# auxboxshield1_42.net
KiCad netlist of a schematic drawn in EAGLE
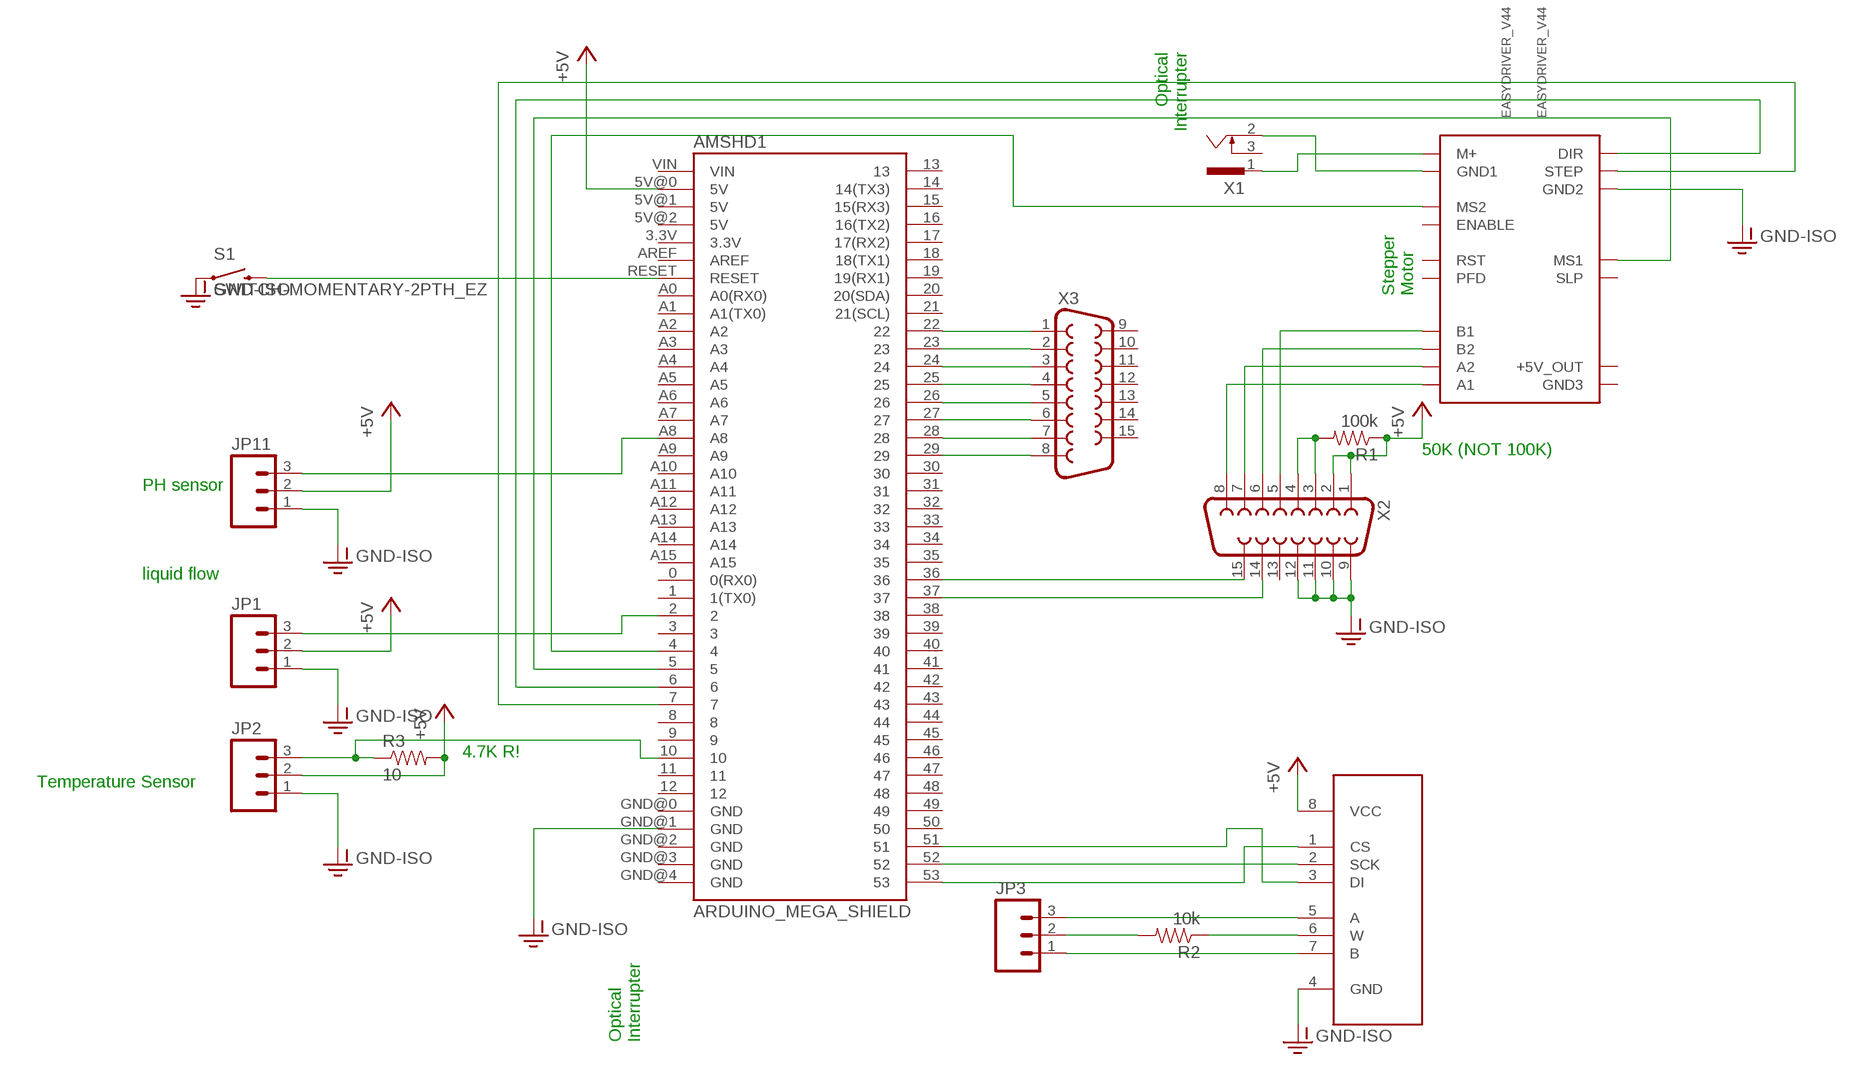
[diagram p0: schematic, sheet 1]

(export (version "E")
  (design (tool "Eeschema 10.0.6"))
  (components
    (comp (ref "AMSHD1")
      (value "ARDUINO_MEGA_SHIELD")
      (footprint "eagle-import:ARDUINO_MEGA_SHIELD")
      (libsource (lib "eagle-import") (part "ARDUINO_MEGA_SHIELD"))
    )
    (comp (ref "EASYDRIVER_V44")
      (value "EASYDRIVER_V44")
      (footprint "eagle-import:EASYDRIVER_V44")
      (libsource (lib "eagle-import") (part "EASYDRIVER_V44"))
    )
    (comp (ref "JP1")
      (value "M03POLAR")
      (footprint "eagle-import:MOLEX-1X3")
      (libsource (lib "eagle-import") (part "M03POLAR"))
    )
    (comp (ref "JP2")
      (value "M03POLAR")
      (footprint "eagle-import:MOLEX-1X3")
      (libsource (lib "eagle-import") (part "M03POLAR"))
    )
    (comp (ref "JP3")
      (value "M03POLAR")
      (footprint "eagle-import:MOLEX-1X3")
      (libsource (lib "eagle-import") (part "M03POLAR"))
    )
    (comp (ref "JP11")
      (value "M03POLAR")
      (footprint "eagle-import:MOLEX-1X3")
      (libsource (lib "eagle-import") (part "M03POLAR"))
    )
    (comp (ref "R1")
      (value "100k")
      (footprint "eagle-import:AXIAL-0.3")
      (libsource (lib "eagle-import") (part "100KOHM-1/4W-5%(PTH)"))
    )
    (comp (ref "R2")
      (value "10k")
      (footprint "eagle-import:AXIAL-0.3")
      (libsource (lib "eagle-import") (part "10KOHM-1/4W-1%(PTH)HORIZ"))
    )
    (comp (ref "R3")
      (value "10")
      (footprint "eagle-import:AXIAL-0.3")
      (libsource (lib "eagle-import") (part "10OHM-1/4W-5%(PTH)"))
    )
    (comp (ref "S1")
      (value "SWITCH-MOMENTARY-2PTH_EZ")
      (footprint "eagle-import:TACTILE-PTH-EZ")
      (libsource (lib "eagle-import") (part "SWITCH-MOMENTARY-2PTH_EZ"))
    )
    (comp (ref "U1")
      (value "MCP41XXX")
      (footprint "eagle-import:SO08")
      (libsource (lib "eagle-import") (part "MCP41XXX"))
    )
    (comp (ref "X1")
      (value "SCD-014A")
      (footprint "eagle-import:SCD-014-A")
      (libsource (lib "eagle-import") (part "SCD-014A"))
    )
    (comp (ref "X2")
      (value "F15HP")
      (footprint "eagle-import:F15HP")
      (libsource (lib "eagle-import") (part "F15HP"))
    )
    (comp (ref "X3")
      (value "F15HP")
      (footprint "eagle-import:F15HP")
      (libsource (lib "eagle-import") (part "F15HP"))
    )
  )
  (nets
    (net (code "1") (name "+5V") (class "Default")
      (node (ref "AMSHD1") (pin "5V@0") (pinfunction "5V_5V@0") (pintype "bidirectional"))
      (node (ref "JP1") (pin "2") (pinfunction "2_2") (pintype "passive"))
      (node (ref "JP11") (pin "2") (pinfunction "2_2") (pintype "passive"))
      (node (ref "JP2") (pin "2") (pinfunction "2_2") (pintype "passive"))
      (node (ref "R1") (pin "P$1") (pinfunction "1_P$1") (pintype "passive"))
      (node (ref "R3") (pin "P$2") (pinfunction "2_P$2") (pintype "passive"))
      (node (ref "U1") (pin "8") (pinfunction "VCC_8") (pintype "bidirectional"))
      (node (ref "X2") (pin "1") (pinfunction "1_1") (pintype "passive"))
      (node (ref "X2") (pin "2") (pinfunction "2_2") (pintype "passive"))
    )
    (net (code "2") (name "GND-ISO") (class "Default")
      (node (ref "AMSHD1") (pin "GND@1") (pinfunction "GND_GND@1") (pintype "bidirectional"))
      (node (ref "EASYDRIVER_V44") (pin "GND2") (pinfunction "GND2_GND2") (pintype "bidirectional"))
      (node (ref "JP1") (pin "1") (pinfunction "1_1") (pintype "passive"))
      (node (ref "JP11") (pin "1") (pinfunction "1_1") (pintype "passive"))
      (node (ref "JP2") (pin "1") (pinfunction "1_1") (pintype "passive"))
      (node (ref "S1") (pin "1") (pinfunction "1_1") (pintype "passive"))
      (node (ref "U1") (pin "4") (pinfunction "GND_4") (pintype "bidirectional"))
      (node (ref "X2") (pin "10") (pinfunction "10_10") (pintype "passive"))
      (node (ref "X2") (pin "11") (pinfunction "11_11") (pintype "passive"))
      (node (ref "X2") (pin "12") (pinfunction "12_12") (pintype "passive"))
      (node (ref "X2") (pin "9") (pinfunction "9_9") (pintype "passive"))
    )
    (net (code "3") (name "Net-(AMSHD1-Pad2)") (class "Default")
      (node (ref "AMSHD1") (pin "2") (pinfunction "2_2") (pintype "bidirectional"))
      (node (ref "JP1") (pin "3") (pinfunction "3_3") (pintype "passive"))
    )
    (net (code "4") (name "Net-(AMSHD1-Pad4)") (class "Default")
      (node (ref "AMSHD1") (pin "4") (pinfunction "4_4") (pintype "bidirectional"))
      (node (ref "EASYDRIVER_V44") (pin "MS2") (pinfunction "MS2_MS2") (pintype "bidirectional"))
    )
    (net (code "5") (name "Net-(AMSHD1-Pad5)") (class "Default")
      (node (ref "AMSHD1") (pin "5") (pinfunction "5_5") (pintype "bidirectional"))
      (node (ref "EASYDRIVER_V44") (pin "MS1") (pinfunction "MS1_MS1") (pintype "bidirectional"))
    )
    (net (code "6") (name "Net-(AMSHD1-Pad6)") (class "Default")
      (node (ref "AMSHD1") (pin "6") (pinfunction "6_6") (pintype "bidirectional"))
      (node (ref "EASYDRIVER_V44") (pin "DIR") (pinfunction "DIR_DIR") (pintype "bidirectional"))
    )
    (net (code "7") (name "Net-(AMSHD1-Pad7)") (class "Default")
      (node (ref "AMSHD1") (pin "7") (pinfunction "7_7") (pintype "bidirectional"))
      (node (ref "EASYDRIVER_V44") (pin "STEP") (pinfunction "STEP_STEP") (pintype "bidirectional"))
    )
    (net (code "8") (name "Net-(AMSHD1-Pad22)") (class "Default")
      (node (ref "AMSHD1") (pin "22") (pinfunction "22_22") (pintype "bidirectional"))
      (node (ref "X3") (pin "1") (pinfunction "1_1") (pintype "passive"))
    )
    (net (code "9") (name "Net-(AMSHD1-Pad23)") (class "Default")
      (node (ref "AMSHD1") (pin "23") (pinfunction "23_23") (pintype "bidirectional"))
      (node (ref "X3") (pin "2") (pinfunction "2_2") (pintype "passive"))
    )
    (net (code "10") (name "Net-(AMSHD1-Pad24)") (class "Default")
      (node (ref "AMSHD1") (pin "24") (pinfunction "24_24") (pintype "bidirectional"))
      (node (ref "X3") (pin "3") (pinfunction "3_3") (pintype "passive"))
    )
    (net (code "11") (name "Net-(AMSHD1-Pad25)") (class "Default")
      (node (ref "AMSHD1") (pin "25") (pinfunction "25_25") (pintype "bidirectional"))
      (node (ref "X3") (pin "4") (pinfunction "4_4") (pintype "passive"))
    )
    (net (code "12") (name "Net-(AMSHD1-Pad26)") (class "Default")
      (node (ref "AMSHD1") (pin "26") (pinfunction "26_26") (pintype "bidirectional"))
      (node (ref "X3") (pin "5") (pinfunction "5_5") (pintype "passive"))
    )
    (net (code "13") (name "Net-(AMSHD1-Pad27)") (class "Default")
      (node (ref "AMSHD1") (pin "27") (pinfunction "27_27") (pintype "bidirectional"))
      (node (ref "X3") (pin "6") (pinfunction "6_6") (pintype "passive"))
    )
    (net (code "14") (name "Net-(AMSHD1-Pad28)") (class "Default")
      (node (ref "AMSHD1") (pin "28") (pinfunction "28_28") (pintype "bidirectional"))
      (node (ref "X3") (pin "7") (pinfunction "7_7") (pintype "passive"))
    )
    (net (code "15") (name "Net-(AMSHD1-Pad29)") (class "Default")
      (node (ref "AMSHD1") (pin "29") (pinfunction "29_29") (pintype "bidirectional"))
      (node (ref "X3") (pin "8") (pinfunction "8_8") (pintype "passive"))
    )
    (net (code "16") (name "Net-(AMSHD1-Pad36)") (class "Default")
      (node (ref "AMSHD1") (pin "36") (pinfunction "36_36") (pintype "bidirectional"))
      (node (ref "X2") (pin "15") (pinfunction "15_15") (pintype "passive"))
    )
    (net (code "17") (name "Net-(AMSHD1-Pad37)") (class "Default")
      (node (ref "AMSHD1") (pin "37") (pinfunction "37_37") (pintype "bidirectional"))
      (node (ref "X2") (pin "14") (pinfunction "14_14") (pintype "passive"))
    )
    (net (code "18") (name "Net-(AMSHD1-PadA8)") (class "Default")
      (node (ref "AMSHD1") (pin "A8") (pinfunction "A8_A8") (pintype "bidirectional"))
      (node (ref "JP11") (pin "3") (pinfunction "3_3") (pintype "passive"))
    )
    (net (code "19") (name "Net-(EASYDRIVER_V44-PadA1)") (class "Default")
      (node (ref "EASYDRIVER_V44") (pin "A1") (pinfunction "A1_A1") (pintype "bidirectional"))
      (node (ref "X2") (pin "8") (pinfunction "8_8") (pintype "passive"))
    )
    (net (code "20") (name "Net-(EASYDRIVER_V44-PadA2)") (class "Default")
      (node (ref "EASYDRIVER_V44") (pin "A2") (pinfunction "A2_A2") (pintype "bidirectional"))
      (node (ref "X2") (pin "7") (pinfunction "7_7") (pintype "passive"))
    )
    (net (code "21") (name "Net-(EASYDRIVER_V44-PadB1)") (class "Default")
      (node (ref "EASYDRIVER_V44") (pin "B1") (pinfunction "B1_B1") (pintype "bidirectional"))
      (node (ref "X2") (pin "5") (pinfunction "5_5") (pintype "passive"))
    )
    (net (code "22") (name "Net-(EASYDRIVER_V44-PadB2)") (class "Default")
      (node (ref "EASYDRIVER_V44") (pin "B2") (pinfunction "B2_B2") (pintype "bidirectional"))
      (node (ref "X2") (pin "6") (pinfunction "6_6") (pintype "passive"))
    )
    (net (code "23") (name "Net-(EASYDRIVER_V44-PadGND1)") (class "Default")
      (node (ref "EASYDRIVER_V44") (pin "GND1") (pinfunction "GND1_GND1") (pintype "bidirectional"))
      (node (ref "X1") (pin "2") (pinfunction "2_2") (pintype "passive"))
    )
    (net (code "24") (name "Net-(EASYDRIVER_V44-PadM+)") (class "Default")
      (node (ref "EASYDRIVER_V44") (pin "M+") (pinfunction "M+_M+") (pintype "bidirectional"))
      (node (ref "X1") (pin "1") (pinfunction "1_1") (pintype "passive"))
    )
    (net (code "25") (name "Net-(R1-2)") (class "Default")
      (node (ref "R1") (pin "P$2") (pinfunction "2_P$2") (pintype "passive"))
      (node (ref "X2") (pin "3") (pinfunction "3_3") (pintype "passive"))
      (node (ref "X2") (pin "4") (pinfunction "4_4") (pintype "passive"))
    )
    (net (code "26") (name "Net-(R2-1)") (class "Default")
      (node (ref "R2") (pin "P$1") (pinfunction "1_P$1") (pintype "passive"))
      (node (ref "U1") (pin "6") (pinfunction "W_6") (pintype "bidirectional"))
    )
    (net (code "27") (name "Net-(R2-2)") (class "Default")
      (node (ref "JP3") (pin "2") (pinfunction "2_2") (pintype "passive"))
      (node (ref "R2") (pin "P$2") (pinfunction "2_P$2") (pintype "passive"))
    )
    (net (code "28") (name "Net-(R3-1)") (class "Default")
      (node (ref "AMSHD1") (pin "10") (pinfunction "10_10") (pintype "bidirectional"))
      (node (ref "JP2") (pin "3") (pinfunction "3_3") (pintype "passive"))
      (node (ref "R3") (pin "P$1") (pinfunction "1_P$1") (pintype "passive"))
    )
    (net (code "29") (name "Net-(S1-2)") (class "Default")
      (node (ref "AMSHD1") (pin "RESET") (pinfunction "RESET_RESET") (pintype "bidirectional"))
      (node (ref "S1") (pin "3") (pinfunction "2_3") (pintype "passive"))
    )
    (net (code "30") (name "Net-(U1-A)") (class "Default")
      (node (ref "JP3") (pin "3") (pinfunction "3_3") (pintype "passive"))
      (node (ref "U1") (pin "5") (pinfunction "A_5") (pintype "bidirectional"))
    )
    (net (code "31") (name "Net-(U1-B)") (class "Default")
      (node (ref "JP3") (pin "1") (pinfunction "1_1") (pintype "passive"))
      (node (ref "U1") (pin "7") (pinfunction "B_7") (pintype "bidirectional"))
    )
    (net (code "32") (name "Net-(U1-CS)") (class "Default")
      (node (ref "AMSHD1") (pin "53") (pinfunction "53_53") (pintype "bidirectional"))
      (node (ref "U1") (pin "1") (pinfunction "CS_1") (pintype "bidirectional"))
    )
    (net (code "33") (name "Net-(U1-DI)") (class "Default")
      (node (ref "AMSHD1") (pin "51") (pinfunction "51_51") (pintype "bidirectional"))
      (node (ref "U1") (pin "3") (pinfunction "DI_3") (pintype "bidirectional"))
    )
    (net (code "34") (name "Net-(U1-SCK)") (class "Default")
      (node (ref "AMSHD1") (pin "52") (pinfunction "52_52") (pintype "bidirectional"))
      (node (ref "U1") (pin "2") (pinfunction "SCK_2") (pintype "bidirectional"))
    )
    (net (code "35") (name "unconnected-(AMSHD1-0(RX0)-Pad0)") (class "Default")
      (node (ref "AMSHD1") (pin "0") (pinfunction "0(RX0)_0") (pintype "bidirectional"))
    )
    (net (code "36") (name "unconnected-(AMSHD1-1(TX0)-Pad1)") (class "Default")
      (node (ref "AMSHD1") (pin "1") (pinfunction "1(TX0)_1") (pintype "bidirectional"))
    )
    (net (code "37") (name "unconnected-(AMSHD1-5V-Pad5V@1)") (class "Default")
      (node (ref "AMSHD1") (pin "5V@1") (pinfunction "5V_5V@1") (pintype "bidirectional"))
    )
    (net (code "38") (name "unconnected-(AMSHD1-5V-Pad5V@2)") (class "Default")
      (node (ref "AMSHD1") (pin "5V@2") (pinfunction "5V_5V@2") (pintype "bidirectional"))
    )
    (net (code "39") (name "unconnected-(AMSHD1-14(TX3)-Pad14)") (class "Default")
      (node (ref "AMSHD1") (pin "14") (pinfunction "14(TX3)_14") (pintype "bidirectional"))
    )
    (net (code "40") (name "unconnected-(AMSHD1-15(RX3)-Pad15)") (class "Default")
      (node (ref "AMSHD1") (pin "15") (pinfunction "15(RX3)_15") (pintype "bidirectional"))
    )
    (net (code "41") (name "unconnected-(AMSHD1-16(TX2)-Pad16)") (class "Default")
      (node (ref "AMSHD1") (pin "16") (pinfunction "16(TX2)_16") (pintype "bidirectional"))
    )
    (net (code "42") (name "unconnected-(AMSHD1-17(RX2)-Pad17)") (class "Default")
      (node (ref "AMSHD1") (pin "17") (pinfunction "17(RX2)_17") (pintype "bidirectional"))
    )
    (net (code "43") (name "unconnected-(AMSHD1-18(TX1)-Pad18)") (class "Default")
      (node (ref "AMSHD1") (pin "18") (pinfunction "18(TX1)_18") (pintype "bidirectional"))
    )
    (net (code "44") (name "unconnected-(AMSHD1-19(RX1)-Pad19)") (class "Default")
      (node (ref "AMSHD1") (pin "19") (pinfunction "19(RX1)_19") (pintype "bidirectional"))
    )
    (net (code "45") (name "unconnected-(AMSHD1-20(SDA)-Pad20)") (class "Default")
      (node (ref "AMSHD1") (pin "20") (pinfunction "20(SDA)_20") (pintype "bidirectional"))
    )
    (net (code "46") (name "unconnected-(AMSHD1-21(SCL)-Pad21)") (class "Default")
      (node (ref "AMSHD1") (pin "21") (pinfunction "21(SCL)_21") (pintype "bidirectional"))
    )
    (net (code "47") (name "unconnected-(AMSHD1-A0(RX0)-PadA0)") (class "Default")
      (node (ref "AMSHD1") (pin "A0") (pinfunction "A0(RX0)_A0") (pintype "bidirectional"))
    )
    (net (code "48") (name "unconnected-(AMSHD1-A1(TX0)-PadA1)") (class "Default")
      (node (ref "AMSHD1") (pin "A1") (pinfunction "A1(TX0)_A1") (pintype "bidirectional"))
    )
    (net (code "49") (name "unconnected-(AMSHD1-GND-PadGND@0)") (class "Default")
      (node (ref "AMSHD1") (pin "GND@0") (pinfunction "GND_GND@0") (pintype "bidirectional"))
    )
    (net (code "50") (name "unconnected-(AMSHD1-GND-PadGND@2)") (class "Default")
      (node (ref "AMSHD1") (pin "GND@2") (pinfunction "GND_GND@2") (pintype "bidirectional"))
    )
    (net (code "51") (name "unconnected-(AMSHD1-GND-PadGND@3)") (class "Default")
      (node (ref "AMSHD1") (pin "GND@3") (pinfunction "GND_GND@3") (pintype "bidirectional"))
    )
    (net (code "52") (name "unconnected-(AMSHD1-GND-PadGND@4)") (class "Default")
      (node (ref "AMSHD1") (pin "GND@4") (pinfunction "GND_GND@4") (pintype "bidirectional"))
    )
    (net (code "53") (name "unconnected-(AMSHD1-Pad3)") (class "Default")
      (node (ref "AMSHD1") (pin "3") (pinfunction "3_3") (pintype "bidirectional"))
    )
    (net (code "54") (name "unconnected-(AMSHD1-Pad3.3V)") (class "Default")
      (node (ref "AMSHD1") (pin "3.3V") (pinfunction "3.3V_3.3V") (pintype "bidirectional"))
    )
    (net (code "55") (name "unconnected-(AMSHD1-Pad8)") (class "Default")
      (node (ref "AMSHD1") (pin "8") (pinfunction "8_8") (pintype "bidirectional"))
    )
    (net (code "56") (name "unconnected-(AMSHD1-Pad9)") (class "Default")
      (node (ref "AMSHD1") (pin "9") (pinfunction "9_9") (pintype "bidirectional"))
    )
    (net (code "57") (name "unconnected-(AMSHD1-Pad11)") (class "Default")
      (node (ref "AMSHD1") (pin "11") (pinfunction "11_11") (pintype "bidirectional"))
    )
    (net (code "58") (name "unconnected-(AMSHD1-Pad12)") (class "Default")
      (node (ref "AMSHD1") (pin "12") (pinfunction "12_12") (pintype "bidirectional"))
    )
    (net (code "59") (name "unconnected-(AMSHD1-Pad13)") (class "Default")
      (node (ref "AMSHD1") (pin "13") (pinfunction "13_13") (pintype "bidirectional"))
    )
    (net (code "60") (name "unconnected-(AMSHD1-Pad30)") (class "Default")
      (node (ref "AMSHD1") (pin "30") (pinfunction "30_30") (pintype "bidirectional"))
    )
    (net (code "61") (name "unconnected-(AMSHD1-Pad31)") (class "Default")
      (node (ref "AMSHD1") (pin "31") (pinfunction "31_31") (pintype "bidirectional"))
    )
    (net (code "62") (name "unconnected-(AMSHD1-Pad32)") (class "Default")
      (node (ref "AMSHD1") (pin "32") (pinfunction "32_32") (pintype "bidirectional"))
    )
    (net (code "63") (name "unconnected-(AMSHD1-Pad33)") (class "Default")
      (node (ref "AMSHD1") (pin "33") (pinfunction "33_33") (pintype "bidirectional"))
    )
    (net (code "64") (name "unconnected-(AMSHD1-Pad34)") (class "Default")
      (node (ref "AMSHD1") (pin "34") (pinfunction "34_34") (pintype "bidirectional"))
    )
    (net (code "65") (name "unconnected-(AMSHD1-Pad35)") (class "Default")
      (node (ref "AMSHD1") (pin "35") (pinfunction "35_35") (pintype "bidirectional"))
    )
    (net (code "66") (name "unconnected-(AMSHD1-Pad38)") (class "Default")
      (node (ref "AMSHD1") (pin "38") (pinfunction "38_38") (pintype "bidirectional"))
    )
    (net (code "67") (name "unconnected-(AMSHD1-Pad39)") (class "Default")
      (node (ref "AMSHD1") (pin "39") (pinfunction "39_39") (pintype "bidirectional"))
    )
    (net (code "68") (name "unconnected-(AMSHD1-Pad40)") (class "Default")
      (node (ref "AMSHD1") (pin "40") (pinfunction "40_40") (pintype "bidirectional"))
    )
    (net (code "69") (name "unconnected-(AMSHD1-Pad41)") (class "Default")
      (node (ref "AMSHD1") (pin "41") (pinfunction "41_41") (pintype "bidirectional"))
    )
    (net (code "70") (name "unconnected-(AMSHD1-Pad42)") (class "Default")
      (node (ref "AMSHD1") (pin "42") (pinfunction "42_42") (pintype "bidirectional"))
    )
    (net (code "71") (name "unconnected-(AMSHD1-Pad43)") (class "Default")
      (node (ref "AMSHD1") (pin "43") (pinfunction "43_43") (pintype "bidirectional"))
    )
    (net (code "72") (name "unconnected-(AMSHD1-Pad44)") (class "Default")
      (node (ref "AMSHD1") (pin "44") (pinfunction "44_44") (pintype "bidirectional"))
    )
    (net (code "73") (name "unconnected-(AMSHD1-Pad45)") (class "Default")
      (node (ref "AMSHD1") (pin "45") (pinfunction "45_45") (pintype "bidirectional"))
    )
    (net (code "74") (name "unconnected-(AMSHD1-Pad46)") (class "Default")
      (node (ref "AMSHD1") (pin "46") (pinfunction "46_46") (pintype "bidirectional"))
    )
    (net (code "75") (name "unconnected-(AMSHD1-Pad47)") (class "Default")
      (node (ref "AMSHD1") (pin "47") (pinfunction "47_47") (pintype "bidirectional"))
    )
    (net (code "76") (name "unconnected-(AMSHD1-Pad48)") (class "Default")
      (node (ref "AMSHD1") (pin "48") (pinfunction "48_48") (pintype "bidirectional"))
    )
    (net (code "77") (name "unconnected-(AMSHD1-Pad49)") (class "Default")
      (node (ref "AMSHD1") (pin "49") (pinfunction "49_49") (pintype "bidirectional"))
    )
    (net (code "78") (name "unconnected-(AMSHD1-Pad50)") (class "Default")
      (node (ref "AMSHD1") (pin "50") (pinfunction "50_50") (pintype "bidirectional"))
    )
    (net (code "79") (name "unconnected-(AMSHD1-PadA2)") (class "Default")
      (node (ref "AMSHD1") (pin "A2") (pinfunction "A2_A2") (pintype "bidirectional"))
    )
    (net (code "80") (name "unconnected-(AMSHD1-PadA3)") (class "Default")
      (node (ref "AMSHD1") (pin "A3") (pinfunction "A3_A3") (pintype "bidirectional"))
    )
    (net (code "81") (name "unconnected-(AMSHD1-PadA4)") (class "Default")
      (node (ref "AMSHD1") (pin "A4") (pinfunction "A4_A4") (pintype "bidirectional"))
    )
    (net (code "82") (name "unconnected-(AMSHD1-PadA5)") (class "Default")
      (node (ref "AMSHD1") (pin "A5") (pinfunction "A5_A5") (pintype "bidirectional"))
    )
    (net (code "83") (name "unconnected-(AMSHD1-PadA6)") (class "Default")
      (node (ref "AMSHD1") (pin "A6") (pinfunction "A6_A6") (pintype "bidirectional"))
    )
    (net (code "84") (name "unconnected-(AMSHD1-PadA7)") (class "Default")
      (node (ref "AMSHD1") (pin "A7") (pinfunction "A7_A7") (pintype "bidirectional"))
    )
    (net (code "85") (name "unconnected-(AMSHD1-PadA9)") (class "Default")
      (node (ref "AMSHD1") (pin "A9") (pinfunction "A9_A9") (pintype "bidirectional"))
    )
    (net (code "86") (name "unconnected-(AMSHD1-PadA10)") (class "Default")
      (node (ref "AMSHD1") (pin "A10") (pinfunction "A10_A10") (pintype "bidirectional"))
    )
    (net (code "87") (name "unconnected-(AMSHD1-PadA11)") (class "Default")
      (node (ref "AMSHD1") (pin "A11") (pinfunction "A11_A11") (pintype "bidirectional"))
    )
    (net (code "88") (name "unconnected-(AMSHD1-PadA12)") (class "Default")
      (node (ref "AMSHD1") (pin "A12") (pinfunction "A12_A12") (pintype "bidirectional"))
    )
    (net (code "89") (name "unconnected-(AMSHD1-PadA13)") (class "Default")
      (node (ref "AMSHD1") (pin "A13") (pinfunction "A13_A13") (pintype "bidirectional"))
    )
    (net (code "90") (name "unconnected-(AMSHD1-PadA14)") (class "Default")
      (node (ref "AMSHD1") (pin "A14") (pinfunction "A14_A14") (pintype "bidirectional"))
    )
    (net (code "91") (name "unconnected-(AMSHD1-PadA15)") (class "Default")
      (node (ref "AMSHD1") (pin "A15") (pinfunction "A15_A15") (pintype "bidirectional"))
    )
    (net (code "92") (name "unconnected-(AMSHD1-PadAREF)") (class "Default")
      (node (ref "AMSHD1") (pin "AREF") (pinfunction "AREF_AREF") (pintype "bidirectional"))
    )
    (net (code "93") (name "unconnected-(AMSHD1-PadVIN)") (class "Default")
      (node (ref "AMSHD1") (pin "VIN") (pinfunction "VIN_VIN") (pintype "bidirectional"))
    )
    (net (code "94") (name "unconnected-(EASYDRIVER_V44-+5V_OUT-PadP$11)") (class "Default")
      (node (ref "EASYDRIVER_V44") (pin "P$11") (pinfunction "+5V_OUT_P$11") (pintype "bidirectional"))
    )
    (net (code "95") (name "unconnected-(EASYDRIVER_V44-PadENABLE)") (class "Default")
      (node (ref "EASYDRIVER_V44") (pin "ENABLE") (pinfunction "ENABLE_ENABLE") (pintype "bidirectional"))
    )
    (net (code "96") (name "unconnected-(EASYDRIVER_V44-PadGND3)") (class "Default")
      (node (ref "EASYDRIVER_V44") (pin "GND3") (pinfunction "GND3_GND3") (pintype "bidirectional"))
    )
    (net (code "97") (name "unconnected-(EASYDRIVER_V44-PadPFD)") (class "Default")
      (node (ref "EASYDRIVER_V44") (pin "PFD") (pinfunction "PFD_PFD") (pintype "bidirectional"))
    )
    (net (code "98") (name "unconnected-(EASYDRIVER_V44-PadRST)") (class "Default")
      (node (ref "EASYDRIVER_V44") (pin "RST") (pinfunction "RST_RST") (pintype "bidirectional"))
    )
    (net (code "99") (name "unconnected-(EASYDRIVER_V44-SLP-PadSLEEP)") (class "Default")
      (node (ref "EASYDRIVER_V44") (pin "SLEEP") (pinfunction "SLP_SLEEP") (pintype "bidirectional"))
    )
    (net (code "100") (name "unconnected-(X1-Pad3)") (class "Default")
      (node (ref "X1") (pin "3") (pinfunction "3_3") (pintype "passive"))
    )
    (net (code "101") (name "unconnected-(X2-Pad13)") (class "Default")
      (node (ref "X2") (pin "13") (pinfunction "13_13") (pintype "passive"))
    )
    (net (code "102") (name "unconnected-(X3-Pad9)") (class "Default")
      (node (ref "X3") (pin "9") (pinfunction "9_9") (pintype "passive"))
    )
    (net (code "103") (name "unconnected-(X3-Pad10)") (class "Default")
      (node (ref "X3") (pin "10") (pinfunction "10_10") (pintype "passive"))
    )
    (net (code "104") (name "unconnected-(X3-Pad11)") (class "Default")
      (node (ref "X3") (pin "11") (pinfunction "11_11") (pintype "passive"))
    )
    (net (code "105") (name "unconnected-(X3-Pad12)") (class "Default")
      (node (ref "X3") (pin "12") (pinfunction "12_12") (pintype "passive"))
    )
    (net (code "106") (name "unconnected-(X3-Pad13)") (class "Default")
      (node (ref "X3") (pin "13") (pinfunction "13_13") (pintype "passive"))
    )
    (net (code "107") (name "unconnected-(X3-Pad14)") (class "Default")
      (node (ref "X3") (pin "14") (pinfunction "14_14") (pintype "passive"))
    )
    (net (code "108") (name "unconnected-(X3-Pad15)") (class "Default")
      (node (ref "X3") (pin "15") (pinfunction "15_15") (pintype "passive"))
    )
  )
)
